# DistanceSensor.net
KiCad netlist of a schematic drawn in EAGLE
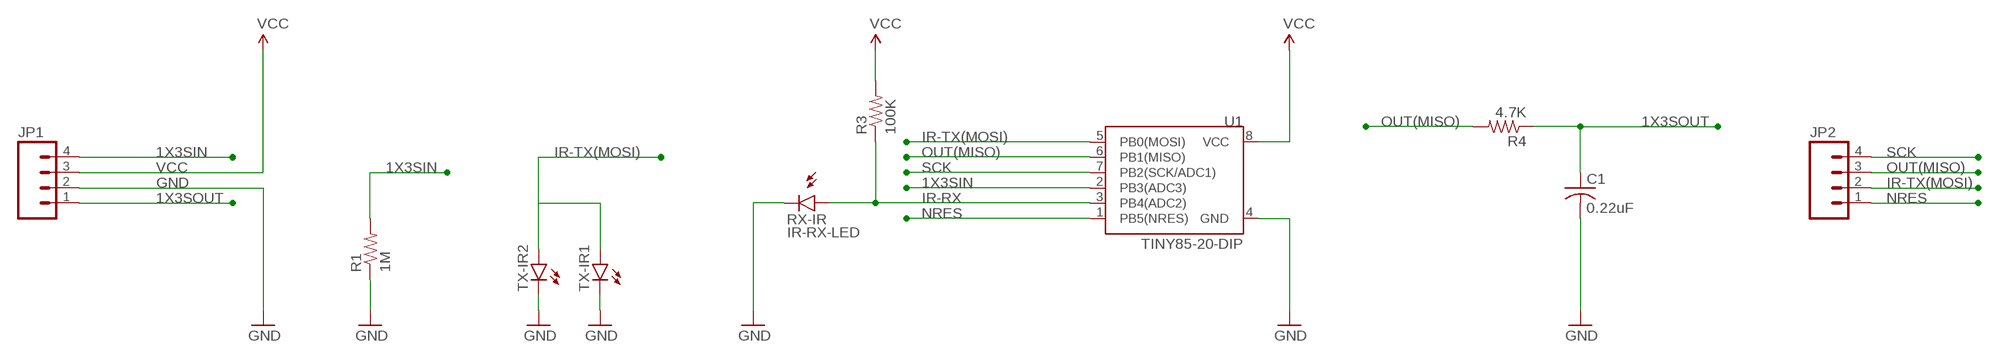
[diagram p0: schematic, sheet 1]

(export (version "E")
  (design (tool "Eeschema 10.0.6"))
  (components
    (comp (ref "C1")
      (value "0.22uF")
      (footprint "eagle-import:C0603")
      (libsource (lib "eagle-import") (part "C-USC0603"))
    )
    (comp (ref "JP1")
      (value "M04PTH")
      (footprint "eagle-import:1X04")
      (libsource (lib "eagle-import") (part "M04PTH"))
    )
    (comp (ref "JP2")
      (value "M04PTH")
      (footprint "eagle-import:1X04")
      (libsource (lib "eagle-import") (part "M04PTH"))
    )
    (comp (ref "R1")
      (value "1M")
      (footprint "eagle-import:R0603")
      (libsource (lib "eagle-import") (part "R-US_R0603"))
    )
    (comp (ref "R3")
      (value "100K")
      (footprint "eagle-import:R0603")
      (libsource (lib "eagle-import") (part "R-US_R0603"))
    )
    (comp (ref "R4")
      (value "4.7K")
      (footprint "eagle-import:R0603")
      (libsource (lib "eagle-import") (part "R-US_R0603"))
    )
    (comp (ref "RX-IR")
      (value "IR-RX-LED")
      (footprint "eagle-import:LED5MM")
      (libsource (lib "eagle-import") (part "IR-RX-LED"))
    )
    (comp (ref "TX-IR1")
      (value "LED5MM")
      (footprint "eagle-import:LED5MM")
      (libsource (lib "eagle-import") (part "LED5MM"))
    )
    (comp (ref "TX-IR2")
      (value "LED5MM")
      (footprint "eagle-import:LED5MM")
      (libsource (lib "eagle-import") (part "LED5MM"))
    )
    (comp (ref "U1")
      (value "TINY85-20-DIP")
      (footprint "eagle-import:DIP08")
      (libsource (lib "eagle-import") (part "ATTINY45TINY85-20-DIP"))
    )
  )
  (nets
    (net (code "1") (name "/1X3SIN") (class "Default")
      (node (ref "JP1") (pin "4") (pinfunction "4_4") (pintype "passive"))
      (node (ref "R1") (pin "2") (pinfunction "2_2") (pintype "passive"))
      (node (ref "U1") (pin "2") (pinfunction "PB3(ADC3)_2") (pintype "bidirectional"))
    )
    (net (code "2") (name "/1X3SOUT") (class "Default")
      (node (ref "C1") (pin "1") (pinfunction "1_1") (pintype "passive"))
      (node (ref "JP1") (pin "1") (pinfunction "1_1") (pintype "passive"))
      (node (ref "R4") (pin "1") (pinfunction "1_1") (pintype "passive"))
    )
    (net (code "3") (name "/IR-RX") (class "Default")
      (node (ref "R3") (pin "1") (pinfunction "1_1") (pintype "passive"))
      (node (ref "RX-IR") (pin "A") (pinfunction "A_A") (pintype "passive"))
      (node (ref "U1") (pin "3") (pinfunction "PB4(ADC2)_3") (pintype "bidirectional"))
    )
    (net (code "4") (name "/IR-TX(MOSI)") (class "Default")
      (node (ref "JP2") (pin "2") (pinfunction "2_2") (pintype "passive"))
      (node (ref "TX-IR1") (pin "A") (pinfunction "A_A") (pintype "passive"))
      (node (ref "TX-IR2") (pin "A") (pinfunction "A_A") (pintype "passive"))
      (node (ref "U1") (pin "5") (pinfunction "PB0(MOSI)_5") (pintype "bidirectional"))
    )
    (net (code "5") (name "/NRES") (class "Default")
      (node (ref "JP2") (pin "1") (pinfunction "1_1") (pintype "passive"))
      (node (ref "U1") (pin "1") (pinfunction "PB5(NRES)_1") (pintype "bidirectional"))
    )
    (net (code "6") (name "/OUT(MISO)") (class "Default")
      (node (ref "JP2") (pin "3") (pinfunction "3_3") (pintype "passive"))
      (node (ref "R4") (pin "2") (pinfunction "2_2") (pintype "passive"))
      (node (ref "U1") (pin "6") (pinfunction "PB1(MISO)_6") (pintype "bidirectional"))
    )
    (net (code "7") (name "/SCK") (class "Default")
      (node (ref "JP2") (pin "4") (pinfunction "4_4") (pintype "passive"))
      (node (ref "U1") (pin "7") (pinfunction "PB2(SCK/ADC1)_7") (pintype "bidirectional"))
    )
    (net (code "8") (name "GND") (class "Default")
      (node (ref "C1") (pin "2") (pinfunction "2_2") (pintype "passive"))
      (node (ref "JP1") (pin "2") (pinfunction "2_2") (pintype "passive"))
      (node (ref "R1") (pin "1") (pinfunction "1_1") (pintype "passive"))
      (node (ref "RX-IR") (pin "K") (pinfunction "C_K") (pintype "passive"))
      (node (ref "TX-IR1") (pin "K") (pinfunction "C_K") (pintype "passive"))
      (node (ref "TX-IR2") (pin "K") (pinfunction "C_K") (pintype "passive"))
      (node (ref "U1") (pin "4") (pinfunction "GND_4") (pintype "bidirectional"))
    )
    (net (code "9") (name "VCC") (class "Default")
      (node (ref "JP1") (pin "3") (pinfunction "3_3") (pintype "passive"))
      (node (ref "R3") (pin "2") (pinfunction "2_2") (pintype "passive"))
      (node (ref "U1") (pin "8") (pinfunction "VCC_8") (pintype "bidirectional"))
    )
  )
)
